# FI_10_7.net
KiCad netlist of a schematic drawn in Altium Designer
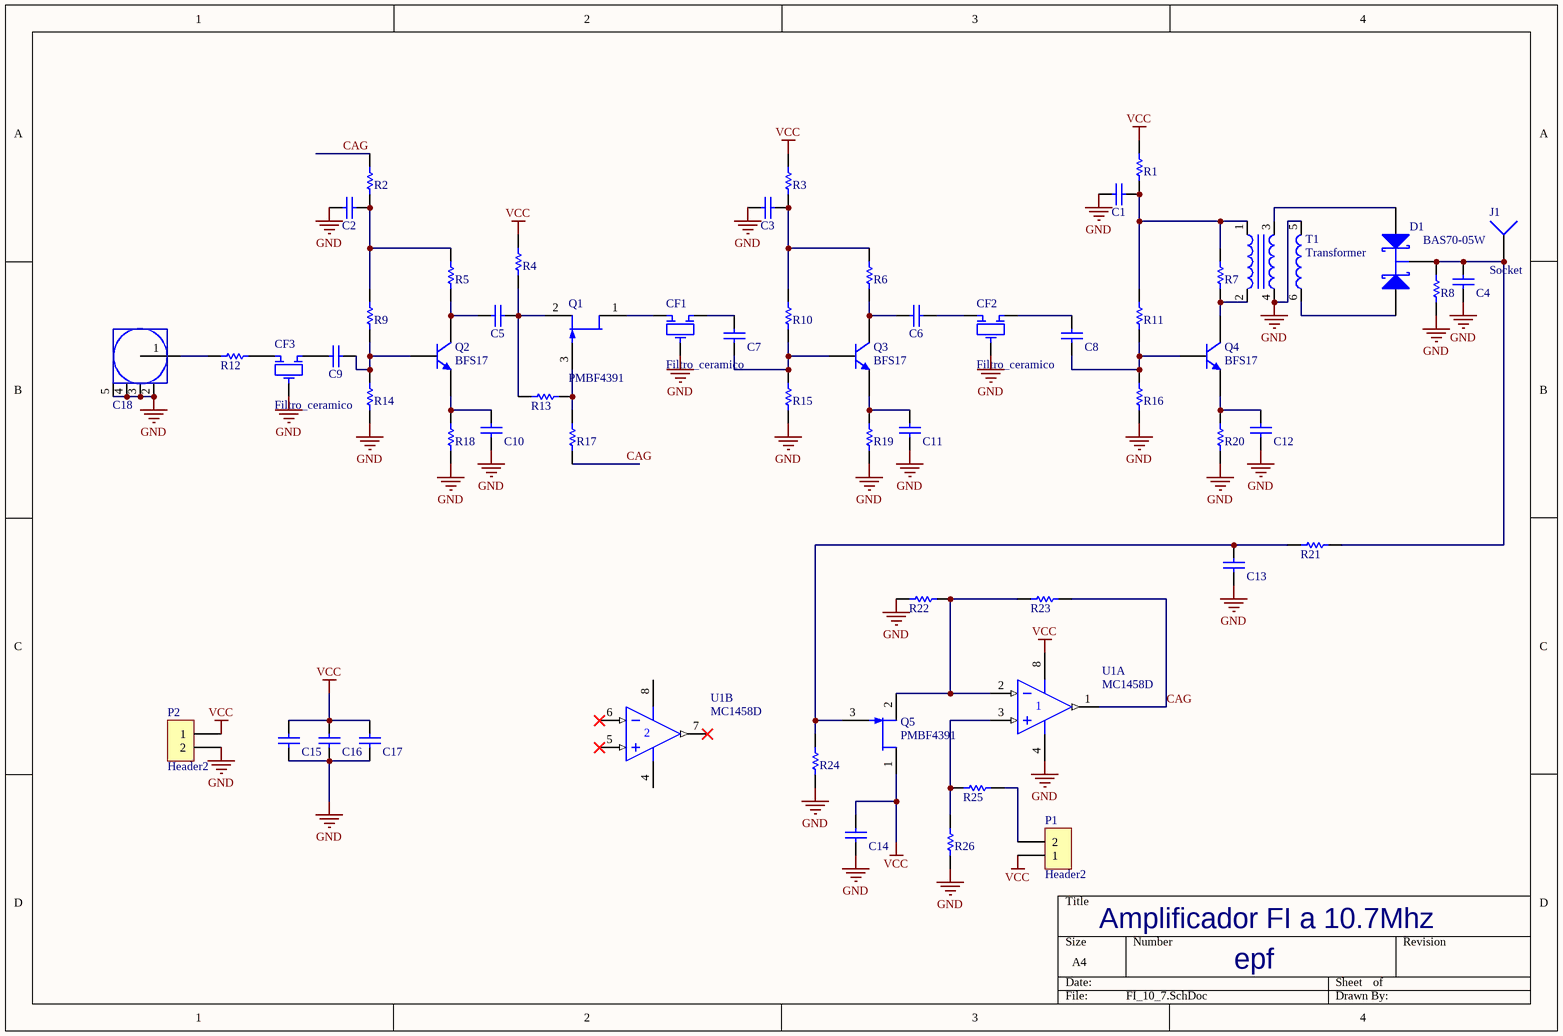
[diagram p0: FI_10_7.SchDoc]

(export (version "E")
  (design (tool "Eeschema 10.0.6"))
  (components
    (comp (ref "C1") (value "Capacitor") (footprint "0805_CAP") (libsource (lib "epf") (part "Cap")))
    (comp (ref "C2") (value "Capacitor") (footprint "0805_CAP") (libsource (lib "epf") (part "Cap")))
    (comp (ref "C3") (value "Capacitor") (footprint "0805_CAP") (libsource (lib "epf") (part "Cap")))
    (comp (ref "C4") (value "Capacitor") (footprint "0805_CAP") (libsource (lib "epf") (part "Cap")))
    (comp (ref "C5") (value "Capacitor") (footprint "0805_CAP") (libsource (lib "epf") (part "Cap")))
    (comp (ref "C6") (value "Capacitor") (footprint "0805_CAP") (libsource (lib "epf") (part "Cap")))
    (comp (ref "C7") (value "Capacitor") (footprint "0805_CAP") (libsource (lib "epf") (part "Cap")))
    (comp (ref "C8") (value "Capacitor") (footprint "0805_CAP") (libsource (lib "epf") (part "Cap")))
    (comp (ref "C9") (value "Capacitor") (footprint "0805_CAP") (libsource (lib "epf") (part "Cap")))
    (comp (ref "C10") (value "Capacitor") (footprint "0805_CAP") (libsource (lib "epf") (part "Cap")))
    (comp (ref "C11") (value "Capacitor") (footprint "0805_CAP") (libsource (lib "epf") (part "Cap")))
    (comp (ref "C12") (value "Capacitor") (footprint "0805_CAP") (libsource (lib "epf") (part "Cap")))
    (comp (ref "C13") (value "Capacitor") (footprint "0805_CAP") (libsource (lib "epf") (part "Cap")))
    (comp (ref "C14") (value "Capacitor") (footprint "0805_CAP") (libsource (lib "epf") (part "Cap")))
    (comp (ref "C15") (value "Capacitor") (footprint "0805_CAP") (libsource (lib "epf") (part "Cap")))
    (comp (ref "C16") (value "Capacitor") (footprint "0805_CAP") (libsource (lib "epf") (part "Cap")))
    (comp (ref "C17") (value "Capacitor") (footprint "0805_CAP") (libsource (lib "epf") (part "Cap")))
    (comp (ref "C18") (value "SMA") (footprint "SMAL2") (libsource (lib "epf") (part "SMA")))
    (comp (ref "CF1")
      (value "Filtro_ceramico")
      (footprint "Filter_10_7")
      (libsource (lib "epf") (part "Filter_10_7"))
    )
    (comp (ref "CF2")
      (value "Filtro_ceramico")
      (footprint "Filter_10_7")
      (libsource (lib "epf") (part "Filter_10_7"))
    )
    (comp (ref "CF3")
      (value "Filtro_ceramico")
      (footprint "Filter_10_7")
      (libsource (lib "epf") (part "Filter_10_7"))
    )
    (comp (ref "D1")
      (value "BAS70-05W")
      (footprint "SOT323_N")
      (description "Schottky Barrier Double Diode")
      (fields (field (name "PUBLISHER") "Altium Limited"))
      (libsource (lib "Philips Discrete Diode - Schottky") (part "BAS70-05W"))
    )
    (comp (ref "J1")
      (value "Socket")
      (footprint "PIN1")
      (fields (field (name "PUBLISHER") "Altium Limited"))
      (libsource (lib "Miscellaneous Connectors") (part "Socket"))
    )
    (comp (ref "P1") (value "Header2") (footprint "Header2Hembra") (libsource (lib "") (part "Header2_1")))
    (comp (ref "P2") (value "Header2") (footprint "Header2Hembra") (libsource (lib "epf") (part "Header2")))
    (comp (ref "Q1")
      (value "PMBF4391")
      (footprint "SOT23")
      (description "N-channel Silicon Junction Field-effect Transistor")
      (fields (field (name "PUBLISHER") "Altium Limited"))
      (libsource (lib "") (part "PMBF4391_1"))
    )
    (comp (ref "Q2")
      (value "BFS17")
      (footprint "SOT23")
      (description "NPN 1 GHz Wideband Transistor")
      (fields (field (name "PUBLISHER") "Altium Limited"))
      (libsource (lib "Philips Discrete BJT - RF Transistor") (part "BFS17"))
    )
    (comp (ref "Q3")
      (value "BFS17")
      (footprint "SOT23")
      (description "NPN 1 GHz Wideband Transistor")
      (fields (field (name "PUBLISHER") "Altium Limited"))
      (libsource (lib "Philips Discrete BJT - RF Transistor") (part "BFS17"))
    )
    (comp (ref "Q4")
      (value "BFS17")
      (footprint "SOT23")
      (description "NPN 1 GHz Wideband Transistor")
      (fields (field (name "PUBLISHER") "Altium Limited"))
      (libsource (lib "Philips Discrete BJT - RF Transistor") (part "BFS17"))
    )
    (comp (ref "Q5")
      (value "PMBF4391")
      (footprint "SOT23")
      (description "N-channel Silicon Junction Field-effect Transistor")
      (fields (field (name "PUBLISHER") "Altium Limited"))
      (libsource (lib "Philips Discrete JFET") (part "PMBF4391"))
    )
    (comp (ref "R1") (value "Resistor") (footprint "0805_RES") (libsource (lib "epf") (part "Res")))
    (comp (ref "R2") (value "Resistor") (footprint "0805_RES") (libsource (lib "epf") (part "Res")))
    (comp (ref "R3") (value "Resistor") (footprint "0805_RES") (libsource (lib "epf") (part "Res")))
    (comp (ref "R4") (value "Resistor") (footprint "0805_RES") (libsource (lib "epf") (part "Res")))
    (comp (ref "R5") (value "Resistor") (footprint "0805_RES") (libsource (lib "epf") (part "Res")))
    (comp (ref "R6") (value "Resistor") (footprint "0805_RES") (libsource (lib "epf") (part "Res")))
    (comp (ref "R7") (value "Resistor") (footprint "0805_RES") (libsource (lib "epf") (part "Res")))
    (comp (ref "R8") (value "Resistor") (footprint "0805_RES") (libsource (lib "epf") (part "Res")))
    (comp (ref "R9") (value "Resistor") (footprint "0805_RES") (libsource (lib "epf") (part "Res")))
    (comp (ref "R10") (value "Resistor") (footprint "0805_RES") (libsource (lib "epf") (part "Res")))
    (comp (ref "R11") (value "Resistor") (footprint "0805_RES") (libsource (lib "epf") (part "Res")))
    (comp (ref "R12") (value "Resistor") (footprint "0805_RES") (libsource (lib "epf") (part "Res")))
    (comp (ref "R13") (value "Resistor") (footprint "0805_RES") (libsource (lib "epf") (part "Res")))
    (comp (ref "R14") (value "Resistor") (footprint "0805_RES") (libsource (lib "epf") (part "Res")))
    (comp (ref "R15") (value "Resistor") (footprint "0805_RES") (libsource (lib "epf") (part "Res")))
    (comp (ref "R16") (value "Resistor") (footprint "0805_RES") (libsource (lib "epf") (part "Res")))
    (comp (ref "R17") (value "Resistor") (footprint "0805_RES") (libsource (lib "epf") (part "Res")))
    (comp (ref "R18") (value "Resistor") (footprint "0805_RES") (libsource (lib "epf") (part "Res")))
    (comp (ref "R19") (value "Resistor") (footprint "0805_RES") (libsource (lib "epf") (part "Res")))
    (comp (ref "R20") (value "Resistor") (footprint "0805_RES") (libsource (lib "epf") (part "Res")))
    (comp (ref "R21") (value "Resistor") (footprint "0805_RES") (libsource (lib "epf") (part "Res")))
    (comp (ref "R22") (value "Resistor") (footprint "0805_RES") (libsource (lib "epf") (part "Res")))
    (comp (ref "R23") (value "Resistor") (footprint "0805_RES") (libsource (lib "epf") (part "Res")))
    (comp (ref "R24") (value "Resistor") (footprint "0805_RES") (libsource (lib "epf") (part "Res")))
    (comp (ref "R25") (value "Resistor") (footprint "0805_RES") (libsource (lib "epf") (part "Res")))
    (comp (ref "R26") (value "Resistor") (footprint "0805_RES") (libsource (lib "epf") (part "Res")))
    (comp (ref "T1")
      (value "Transformer")
      (footprint "NTH12_V_3Ind_2")
      (description "Transformador 3 bobinas")
      (libsource (lib "epf") (part "Transformador3"))
    )
    (comp (ref "U1")
      (value "MC1458D")
      (footprint "751-05_M")
      (description "Dual Operational Amplifier, Internally Compensated")
      (fields (field (name "PUBLISHER") "Altium Limited"))
      (libsource (lib "Motorola Amplifier Operational Amplifier") (part "MC1458D"))
    )
  )
  (nets
    (net (code "1") (name "/CAG") (class "Default")
      (node (ref "R17") (pin "1") (pinfunction "1_1") (pintype "passive"))
      (node (ref "R2") (pin "1") (pinfunction "1_1") (pintype "passive"))
      (node (ref "R23") (pin "2") (pinfunction "2_2") (pintype "passive"))
      (node (ref "U1") (pin "1") (pinfunction "OUT_1") (pintype "output"))
    )
    (net (code "2") (name "GND") (class "Default")
      (node (ref "C1") (pin "2") (pinfunction "2_2") (pintype "passive"))
      (node (ref "C10") (pin "1") (pinfunction "1_1") (pintype "passive"))
      (node (ref "C11") (pin "1") (pinfunction "1_1") (pintype "passive"))
      (node (ref "C12") (pin "1") (pinfunction "1_1") (pintype "passive"))
      (node (ref "C13") (pin "1") (pinfunction "1_1") (pintype "passive"))
      (node (ref "C14") (pin "1") (pinfunction "1_1") (pintype "passive"))
      (node (ref "C15") (pin "1") (pinfunction "1_1") (pintype "passive"))
      (node (ref "C16") (pin "1") (pinfunction "1_1") (pintype "passive"))
      (node (ref "C17") (pin "1") (pinfunction "1_1") (pintype "passive"))
      (node (ref "C18") (pin "2") (pinfunction "GND_2") (pintype "passive"))
      (node (ref "C18") (pin "3") (pinfunction "GND_3") (pintype "passive"))
      (node (ref "C18") (pin "4") (pinfunction "GND_4") (pintype "passive"))
      (node (ref "C18") (pin "5") (pinfunction "GND_5") (pintype "passive"))
      (node (ref "C2") (pin "2") (pinfunction "2_2") (pintype "passive"))
      (node (ref "C3") (pin "2") (pinfunction "2_2") (pintype "passive"))
      (node (ref "C4") (pin "1") (pinfunction "1_1") (pintype "passive"))
      (node (ref "CF1") (pin "2") (pinfunction "2_2") (pintype "passive"))
      (node (ref "CF2") (pin "2") (pinfunction "2_2") (pintype "passive"))
      (node (ref "CF3") (pin "2") (pinfunction "2_2") (pintype "passive"))
      (node (ref "P2") (pin "2") (pinfunction "2_2") (pintype "passive"))
      (node (ref "R14") (pin "2") (pinfunction "2_2") (pintype "passive"))
      (node (ref "R15") (pin "2") (pinfunction "2_2") (pintype "passive"))
      (node (ref "R16") (pin "2") (pinfunction "2_2") (pintype "passive"))
      (node (ref "R18") (pin "2") (pinfunction "2_2") (pintype "passive"))
      (node (ref "R19") (pin "2") (pinfunction "2_2") (pintype "passive"))
      (node (ref "R20") (pin "2") (pinfunction "2_2") (pintype "passive"))
      (node (ref "R22") (pin "1") (pinfunction "1_1") (pintype "passive"))
      (node (ref "R24") (pin "1") (pinfunction "1_1") (pintype "passive"))
      (node (ref "R26") (pin "1") (pinfunction "1_1") (pintype "passive"))
      (node (ref "R8") (pin "2") (pinfunction "2_2") (pintype "passive"))
      (node (ref "T1") (pin "4") (pinfunction "4_4") (pintype "passive"))
      (node (ref "T1") (pin "5") (pinfunction "5_5") (pintype "passive"))
      (node (ref "U1") (pin "4") (pinfunction "V-_4") (pintype "power_in"))
    )
    (net (code "3") (name "Net-(C1-Pad1)") (class "Default")
      (node (ref "C1") (pin "1") (pinfunction "1_1") (pintype "passive"))
      (node (ref "R1") (pin "2") (pinfunction "2_2") (pintype "passive"))
      (node (ref "R11") (pin "1") (pinfunction "1_1") (pintype "passive"))
      (node (ref "R7") (pin "1") (pinfunction "1_1") (pintype "passive"))
      (node (ref "T1") (pin "1") (pinfunction "1_1") (pintype "passive"))
    )
    (net (code "4") (name "Net-(C2-Pad1)") (class "Default")
      (node (ref "C2") (pin "1") (pinfunction "1_1") (pintype "passive"))
      (node (ref "R2") (pin "2") (pinfunction "2_2") (pintype "passive"))
      (node (ref "R5") (pin "1") (pinfunction "1_1") (pintype "passive"))
      (node (ref "R9") (pin "1") (pinfunction "1_1") (pintype "passive"))
    )
    (net (code "5") (name "Net-(C3-Pad1)") (class "Default")
      (node (ref "C3") (pin "1") (pinfunction "1_1") (pintype "passive"))
      (node (ref "R10") (pin "1") (pinfunction "1_1") (pintype "passive"))
      (node (ref "R3") (pin "2") (pinfunction "2_2") (pintype "passive"))
      (node (ref "R6") (pin "1") (pinfunction "1_1") (pintype "passive"))
    )
    (net (code "6") (name "Net-(C6-Pad1)") (class "Default")
      (node (ref "C6") (pin "1") (pinfunction "1_1") (pintype "passive"))
      (node (ref "CF2") (pin "1") (pinfunction "1_1") (pintype "passive"))
    )
    (net (code "7") (name "Net-(C7-Pad1)") (class "Default")
      (node (ref "C7") (pin "1") (pinfunction "1_1") (pintype "passive"))
      (node (ref "CF1") (pin "3") (pinfunction "3_3") (pintype "passive"))
    )
    (net (code "8") (name "Net-(C8-Pad2)") (class "Default")
      (node (ref "C8") (pin "2") (pinfunction "2_2") (pintype "passive"))
      (node (ref "CF2") (pin "3") (pinfunction "3_3") (pintype "passive"))
    )
    (net (code "9") (name "Net-(C9-Pad2)") (class "Default")
      (node (ref "C9") (pin "2") (pinfunction "2_2") (pintype "passive"))
      (node (ref "CF3") (pin "3") (pinfunction "3_3") (pintype "passive"))
    )
    (net (code "10") (name "Net-(C18-RF)") (class "Default")
      (node (ref "C18") (pin "1") (pinfunction "RF_1") (pintype "passive"))
      (node (ref "R12") (pin "1") (pinfunction "1_1") (pintype "passive"))
    )
    (net (code "11") (name "Net-(CF3-Pad1)") (class "Default")
      (node (ref "CF3") (pin "1") (pinfunction "1_1") (pintype "passive"))
      (node (ref "R12") (pin "2") (pinfunction "2_2") (pintype "passive"))
    )
    (net (code "12") (name "Net-(D1-A1)") (class "Default")
      (node (ref "D1") (pin "1") (pinfunction "A1_1") (pintype "passive"))
      (node (ref "T1") (pin "3") (pinfunction "3_3") (pintype "passive"))
    )
    (net (code "13") (name "Net-(D1-A2)") (class "Default")
      (node (ref "D1") (pin "2") (pinfunction "A2_2") (pintype "passive"))
      (node (ref "T1") (pin "6") (pinfunction "6_6") (pintype "passive"))
    )
    (net (code "14") (name "Net-(D1-K)") (class "Default")
      (node (ref "C4") (pin "2") (pinfunction "2_2") (pintype "passive"))
      (node (ref "D1") (pin "3") (pinfunction "K_3") (pintype "passive"))
      (node (ref "J1") (pin "1") (pinfunction "1_1") (pintype "passive"))
      (node (ref "R21") (pin "2") (pinfunction "2_2") (pintype "passive"))
      (node (ref "R8") (pin "1") (pinfunction "1_1") (pintype "passive"))
    )
    (net (code "15") (name "Net-(P1-Pad2)") (class "Default")
      (node (ref "P1") (pin "2") (pinfunction "2_2") (pintype "passive"))
      (node (ref "R25") (pin "2") (pinfunction "2_2") (pintype "passive"))
    )
    (net (code "16") (name "Net-(Q1-D)") (class "Default")
      (node (ref "CF1") (pin "1") (pinfunction "1_1") (pintype "passive"))
      (node (ref "Q1") (pin "1") (pinfunction "D_1") (pintype "passive"))
    )
    (net (code "17") (name "Net-(Q1-G)") (class "Default")
      (node (ref "Q1") (pin "3") (pinfunction "G_3") (pintype "passive"))
      (node (ref "R13") (pin "1") (pinfunction "1_1") (pintype "passive"))
      (node (ref "R17") (pin "2") (pinfunction "2_2") (pintype "passive"))
    )
    (net (code "18") (name "Net-(Q1-S)") (class "Default")
      (node (ref "C5") (pin "1") (pinfunction "1_1") (pintype "passive"))
      (node (ref "Q1") (pin "2") (pinfunction "S_2") (pintype "passive"))
      (node (ref "R13") (pin "2") (pinfunction "2_2") (pintype "passive"))
      (node (ref "R4") (pin "2") (pinfunction "2_2") (pintype "passive"))
    )
    (net (code "19") (name "Net-(Q2-B)") (class "Default")
      (node (ref "C9") (pin "1") (pinfunction "1_1") (pintype "passive"))
      (node (ref "Q2") (pin "1") (pinfunction "B_1") (pintype "passive"))
      (node (ref "R14") (pin "1") (pinfunction "1_1") (pintype "passive"))
      (node (ref "R9") (pin "2") (pinfunction "2_2") (pintype "passive"))
    )
    (net (code "20") (name "Net-(Q2-C)") (class "Default")
      (node (ref "C5") (pin "2") (pinfunction "2_2") (pintype "passive"))
      (node (ref "Q2") (pin "3") (pinfunction "C_3") (pintype "passive"))
      (node (ref "R5") (pin "2") (pinfunction "2_2") (pintype "passive"))
    )
    (net (code "21") (name "Net-(Q2-E)") (class "Default")
      (node (ref "C10") (pin "2") (pinfunction "2_2") (pintype "passive"))
      (node (ref "Q2") (pin "2") (pinfunction "E_2") (pintype "passive"))
      (node (ref "R18") (pin "1") (pinfunction "1_1") (pintype "passive"))
    )
    (net (code "22") (name "Net-(Q3-B)") (class "Default")
      (node (ref "C7") (pin "2") (pinfunction "2_2") (pintype "passive"))
      (node (ref "Q3") (pin "1") (pinfunction "B_1") (pintype "passive"))
      (node (ref "R10") (pin "2") (pinfunction "2_2") (pintype "passive"))
      (node (ref "R15") (pin "1") (pinfunction "1_1") (pintype "passive"))
    )
    (net (code "23") (name "Net-(Q3-C)") (class "Default")
      (node (ref "C6") (pin "2") (pinfunction "2_2") (pintype "passive"))
      (node (ref "Q3") (pin "3") (pinfunction "C_3") (pintype "passive"))
      (node (ref "R6") (pin "2") (pinfunction "2_2") (pintype "passive"))
    )
    (net (code "24") (name "Net-(Q3-E)") (class "Default")
      (node (ref "C11") (pin "2") (pinfunction "2_2") (pintype "passive"))
      (node (ref "Q3") (pin "2") (pinfunction "E_2") (pintype "passive"))
      (node (ref "R19") (pin "1") (pinfunction "1_1") (pintype "passive"))
    )
    (net (code "25") (name "Net-(Q4-B)") (class "Default")
      (node (ref "C8") (pin "1") (pinfunction "1_1") (pintype "passive"))
      (node (ref "Q4") (pin "1") (pinfunction "B_1") (pintype "passive"))
      (node (ref "R11") (pin "2") (pinfunction "2_2") (pintype "passive"))
      (node (ref "R16") (pin "1") (pinfunction "1_1") (pintype "passive"))
    )
    (net (code "26") (name "Net-(Q4-C)") (class "Default")
      (node (ref "Q4") (pin "3") (pinfunction "C_3") (pintype "passive"))
      (node (ref "R7") (pin "2") (pinfunction "2_2") (pintype "passive"))
      (node (ref "T1") (pin "2") (pinfunction "2_2") (pintype "passive"))
    )
    (net (code "27") (name "Net-(Q4-E)") (class "Default")
      (node (ref "C12") (pin "2") (pinfunction "2_2") (pintype "passive"))
      (node (ref "Q4") (pin "2") (pinfunction "E_2") (pintype "passive"))
      (node (ref "R20") (pin "1") (pinfunction "1_1") (pintype "passive"))
    )
    (net (code "28") (name "Net-(Q5-G)") (class "Default")
      (node (ref "C13") (pin "2") (pinfunction "2_2") (pintype "passive"))
      (node (ref "Q5") (pin "3") (pinfunction "G_3") (pintype "passive"))
      (node (ref "R21") (pin "1") (pinfunction "1_1") (pintype "passive"))
      (node (ref "R24") (pin "2") (pinfunction "2_2") (pintype "passive"))
    )
    (net (code "29") (name "Net-(Q5-S)") (class "Default")
      (node (ref "Q5") (pin "2") (pinfunction "S_2") (pintype "passive"))
      (node (ref "R22") (pin "2") (pinfunction "2_2") (pintype "passive"))
      (node (ref "R23") (pin "1") (pinfunction "1_1") (pintype "passive"))
      (node (ref "U1") (pin "2") (pinfunction "IN-_2") (pintype "input"))
    )
    (net (code "30") (name "Net-(U1A-IN+)") (class "Default")
      (node (ref "R25") (pin "1") (pinfunction "1_1") (pintype "passive"))
      (node (ref "R26") (pin "2") (pinfunction "2_2") (pintype "passive"))
      (node (ref "U1") (pin "3") (pinfunction "IN+_3") (pintype "input"))
    )
    (net (code "31") (name "VCC") (class "Default")
      (node (ref "C14") (pin "2") (pinfunction "2_2") (pintype "passive"))
      (node (ref "C15") (pin "2") (pinfunction "2_2") (pintype "passive"))
      (node (ref "C16") (pin "2") (pinfunction "2_2") (pintype "passive"))
      (node (ref "C17") (pin "2") (pinfunction "2_2") (pintype "passive"))
      (node (ref "P1") (pin "1") (pinfunction "1_1") (pintype "passive"))
      (node (ref "P2") (pin "1") (pinfunction "1_1") (pintype "passive"))
      (node (ref "Q5") (pin "1") (pinfunction "D_1") (pintype "passive"))
      (node (ref "R1") (pin "1") (pinfunction "1_1") (pintype "passive"))
      (node (ref "R3") (pin "1") (pinfunction "1_1") (pintype "passive"))
      (node (ref "R4") (pin "1") (pinfunction "1_1") (pintype "passive"))
      (node (ref "U1") (pin "8") (pinfunction "V+_8") (pintype "power_in"))
    )
    (net (code "32") (name "unconnected-(U1B-IN+-Pad5)") (class "Default")
      (node (ref "U1") (pin "5") (pinfunction "IN+_5") (pintype "input+no_connect"))
    )
    (net (code "33") (name "unconnected-(U1B-IN--Pad6)") (class "Default")
      (node (ref "U1") (pin "6") (pinfunction "IN-_6") (pintype "input+no_connect"))
    )
    (net (code "34") (name "unconnected-(U1B-OUT-Pad7)") (class "Default")
      (node (ref "U1") (pin "7") (pinfunction "OUT_7") (pintype "output+no_connect"))
    )
    (net (code "35") (name "unconnected-(U1B-V+-Pad8)") (class "Default")
      (node (ref "U1") (pin "8") (pinfunction "V+_8") (pintype "power_in"))
    )
    (net (code "36") (name "unconnected-(U1B-V--Pad4)") (class "Default")
      (node (ref "U1") (pin "4") (pinfunction "V-_4") (pintype "power_in"))
    )
  )
)
